# 3level_2NX_interleaved_boost_converter.net
KiCad netlist of a schematic drawn in EAGLE
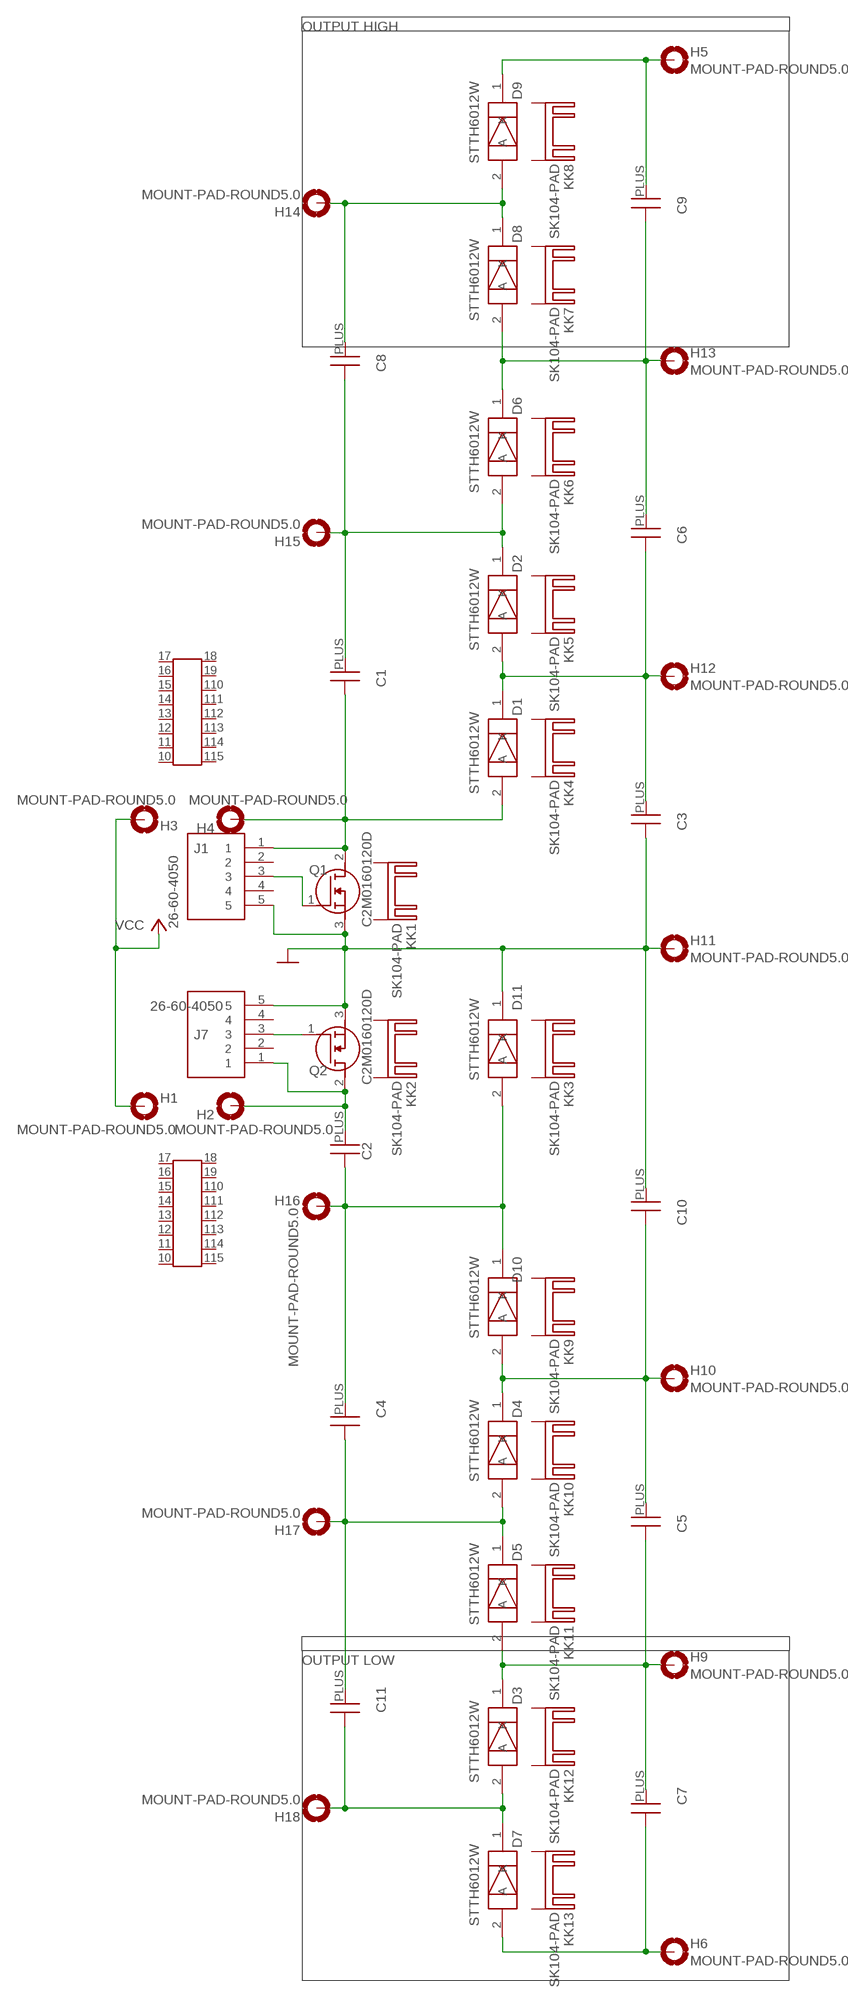
[diagram p0: schematic, sheet 1]
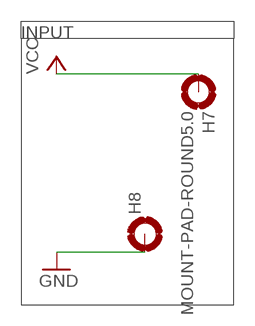
[diagram p1: schematic, sheet 2]

(export (version "E")
  (design (tool "Eeschema 10.0.6"))
  (components
    (comp (ref "H7")
      (value "MOUNT-PAD-ROUND5.0")
      (footprint "eagle-import:5,0-PAD")
      (libsource (lib "eagle-import") (part "MOUNT-PAD-ROUND5.0"))
    )
    (comp (ref "H8")
      (value "MOUNT-PAD-ROUND5.0")
      (footprint "eagle-import:5,0-PAD")
      (libsource (lib "eagle-import") (part "MOUNT-PAD-ROUND5.0"))
    )
    (comp (ref "C1")
      (value "SANJEECAP")
      (footprint "eagle-import:ECA2WHG2R2")
      (libsource (lib "eagle-import") (part "SANJEECAP"))
    )
    (comp (ref "C2")
      (value "SANJEECAP")
      (footprint "eagle-import:ECA2WHG2R2")
      (libsource (lib "eagle-import") (part "SANJEECAP"))
    )
    (comp (ref "C3")
      (value "SANJEECAP")
      (footprint "eagle-import:ECA2WHG2R2")
      (libsource (lib "eagle-import") (part "SANJEECAP"))
    )
    (comp (ref "C4")
      (value "SANJEECAP")
      (footprint "eagle-import:ECA2WHG2R2")
      (libsource (lib "eagle-import") (part "SANJEECAP"))
    )
    (comp (ref "C5")
      (value "SANJEECAP")
      (footprint "eagle-import:ECA2WHG2R2")
      (libsource (lib "eagle-import") (part "SANJEECAP"))
    )
    (comp (ref "C6")
      (value "SANJEECAP")
      (footprint "eagle-import:ECA2WHG2R2")
      (libsource (lib "eagle-import") (part "SANJEECAP"))
    )
    (comp (ref "C7")
      (value "SANJEECAP")
      (footprint "eagle-import:ECA2WHG2R2")
      (libsource (lib "eagle-import") (part "SANJEECAP"))
    )
    (comp (ref "C8")
      (value "SANJEECAP")
      (footprint "eagle-import:ECA2WHG2R2")
      (libsource (lib "eagle-import") (part "SANJEECAP"))
    )
    (comp (ref "C9")
      (value "SANJEECAP")
      (footprint "eagle-import:ECA2WHG2R2")
      (libsource (lib "eagle-import") (part "SANJEECAP"))
    )
    (comp (ref "C10")
      (value "SANJEECAP")
      (footprint "eagle-import:ECA2WHG2R2")
      (libsource (lib "eagle-import") (part "SANJEECAP"))
    )
    (comp (ref "C11")
      (value "SANJEECAP")
      (footprint "eagle-import:ECA2WHG2R2")
      (libsource (lib "eagle-import") (part "SANJEECAP"))
    )
    (comp (ref "D1")
      (value "STTH6012W")
      (footprint "eagle-import:TO1090P515X1560X2445-2P")
      (fields (field (name "RS_PART_NUMBER") "6870818"))
      (libsource (lib "eagle-import") (part "STTH6012W"))
    )
    (comp (ref "D2")
      (value "STTH6012W")
      (footprint "eagle-import:TO1090P515X1560X2445-2P")
      (fields (field (name "RS_PART_NUMBER") "6870818"))
      (libsource (lib "eagle-import") (part "STTH6012W"))
    )
    (comp (ref "D3")
      (value "STTH6012W")
      (footprint "eagle-import:TO1090P515X1560X2445-2P")
      (fields (field (name "RS_PART_NUMBER") "6870818"))
      (libsource (lib "eagle-import") (part "STTH6012W"))
    )
    (comp (ref "D4")
      (value "STTH6012W")
      (footprint "eagle-import:TO1090P515X1560X2445-2P")
      (fields (field (name "RS_PART_NUMBER") "6870818"))
      (libsource (lib "eagle-import") (part "STTH6012W"))
    )
    (comp (ref "D5")
      (value "STTH6012W")
      (footprint "eagle-import:TO1090P515X1560X2445-2P")
      (fields (field (name "RS_PART_NUMBER") "6870818"))
      (libsource (lib "eagle-import") (part "STTH6012W"))
    )
    (comp (ref "D6")
      (value "STTH6012W")
      (footprint "eagle-import:TO1090P515X1560X2445-2P")
      (fields (field (name "RS_PART_NUMBER") "6870818"))
      (libsource (lib "eagle-import") (part "STTH6012W"))
    )
    (comp (ref "D7")
      (value "STTH6012W")
      (footprint "eagle-import:TO1090P515X1560X2445-2P")
      (fields (field (name "RS_PART_NUMBER") "6870818"))
      (libsource (lib "eagle-import") (part "STTH6012W"))
    )
    (comp (ref "D8")
      (value "STTH6012W")
      (footprint "eagle-import:TO1090P515X1560X2445-2P")
      (fields (field (name "RS_PART_NUMBER") "6870818"))
      (libsource (lib "eagle-import") (part "STTH6012W"))
    )
    (comp (ref "D9")
      (value "STTH6012W")
      (footprint "eagle-import:TO1090P515X1560X2445-2P")
      (fields (field (name "RS_PART_NUMBER") "6870818"))
      (libsource (lib "eagle-import") (part "STTH6012W"))
    )
    (comp (ref "D10")
      (value "STTH6012W")
      (footprint "eagle-import:TO1090P515X1560X2445-2P")
      (fields (field (name "RS_PART_NUMBER") "6870818"))
      (libsource (lib "eagle-import") (part "STTH6012W"))
    )
    (comp (ref "D11")
      (value "STTH6012W")
      (footprint "eagle-import:TO1090P515X1560X2445-2P")
      (fields (field (name "RS_PART_NUMBER") "6870818"))
      (libsource (lib "eagle-import") (part "STTH6012W"))
    )
    (comp (ref "H1")
      (value "MOUNT-PAD-ROUND5.0")
      (footprint "eagle-import:5,0-PAD")
      (libsource (lib "eagle-import") (part "MOUNT-PAD-ROUND5.0"))
    )
    (comp (ref "H2")
      (value "MOUNT-PAD-ROUND5.0")
      (footprint "eagle-import:5,0-PAD")
      (libsource (lib "eagle-import") (part "MOUNT-PAD-ROUND5.0"))
    )
    (comp (ref "H3")
      (value "MOUNT-PAD-ROUND5.0")
      (footprint "eagle-import:5,0-PAD")
      (libsource (lib "eagle-import") (part "MOUNT-PAD-ROUND5.0"))
    )
    (comp (ref "H4")
      (value "MOUNT-PAD-ROUND5.0")
      (footprint "eagle-import:5,0-PAD")
      (libsource (lib "eagle-import") (part "MOUNT-PAD-ROUND5.0"))
    )
    (comp (ref "H5")
      (value "MOUNT-PAD-ROUND5.0")
      (footprint "eagle-import:5,0-PAD")
      (libsource (lib "eagle-import") (part "MOUNT-PAD-ROUND5.0"))
    )
    (comp (ref "H6")
      (value "MOUNT-PAD-ROUND5.0")
      (footprint "eagle-import:5,0-PAD")
      (libsource (lib "eagle-import") (part "MOUNT-PAD-ROUND5.0"))
    )
    (comp (ref "H9")
      (value "MOUNT-PAD-ROUND5.0")
      (footprint "eagle-import:5,0-PAD")
      (libsource (lib "eagle-import") (part "MOUNT-PAD-ROUND5.0"))
    )
    (comp (ref "H10")
      (value "MOUNT-PAD-ROUND5.0")
      (footprint "eagle-import:5,0-PAD")
      (libsource (lib "eagle-import") (part "MOUNT-PAD-ROUND5.0"))
    )
    (comp (ref "H11")
      (value "MOUNT-PAD-ROUND5.0")
      (footprint "eagle-import:5,0-PAD")
      (libsource (lib "eagle-import") (part "MOUNT-PAD-ROUND5.0"))
    )
    (comp (ref "H12")
      (value "MOUNT-PAD-ROUND5.0")
      (footprint "eagle-import:5,0-PAD")
      (libsource (lib "eagle-import") (part "MOUNT-PAD-ROUND5.0"))
    )
    (comp (ref "H13")
      (value "MOUNT-PAD-ROUND5.0")
      (footprint "eagle-import:5,0-PAD")
      (libsource (lib "eagle-import") (part "MOUNT-PAD-ROUND5.0"))
    )
    (comp (ref "H14")
      (value "MOUNT-PAD-ROUND5.0")
      (footprint "eagle-import:5,0-PAD")
      (libsource (lib "eagle-import") (part "MOUNT-PAD-ROUND5.0"))
    )
    (comp (ref "H15")
      (value "MOUNT-PAD-ROUND5.0")
      (footprint "eagle-import:5,0-PAD")
      (libsource (lib "eagle-import") (part "MOUNT-PAD-ROUND5.0"))
    )
    (comp (ref "H16")
      (value "MOUNT-PAD-ROUND5.0")
      (footprint "eagle-import:5,0-PAD")
      (libsource (lib "eagle-import") (part "MOUNT-PAD-ROUND5.0"))
    )
    (comp (ref "H17")
      (value "MOUNT-PAD-ROUND5.0")
      (footprint "eagle-import:5,0-PAD")
      (libsource (lib "eagle-import") (part "MOUNT-PAD-ROUND5.0"))
    )
    (comp (ref "H18")
      (value "MOUNT-PAD-ROUND5.0")
      (footprint "eagle-import:5,0-PAD")
      (libsource (lib "eagle-import") (part "MOUNT-PAD-ROUND5.0"))
    )
    (comp (ref "J1")
      (value "26-60-4050")
      (footprint "eagle-import:SHDR5W155P0X396_1X5_1966X1001X")
      (fields (field (name "MOUSER_PART_NUMBER") "538-26-60-4050"))
      (libsource (lib "eagle-import") (part "26-60-4050"))
    )
    (comp (ref "J7")
      (value "26-60-4050")
      (footprint "eagle-import:SHDR5W155P0X396_1X5_1966X1001X")
      (fields (field (name "MOUSER_PART_NUMBER") "538-26-60-4050"))
      (libsource (lib "eagle-import") (part "26-60-4050"))
    )
    (comp (ref "KK1")
      (value "SK104-PAD")
      (footprint "eagle-import:SK104-PAD")
      (libsource (lib "eagle-import") (part "SK104-PAD"))
    )
    (comp (ref "KK2")
      (value "SK104-PAD")
      (footprint "eagle-import:SK104-PAD")
      (libsource (lib "eagle-import") (part "SK104-PAD"))
    )
    (comp (ref "KK3")
      (value "SK104-PAD")
      (footprint "eagle-import:SK104-PAD")
      (libsource (lib "eagle-import") (part "SK104-PAD"))
    )
    (comp (ref "KK4")
      (value "SK104-PAD")
      (footprint "eagle-import:SK104-PAD")
      (libsource (lib "eagle-import") (part "SK104-PAD"))
    )
    (comp (ref "KK5")
      (value "SK104-PAD")
      (footprint "eagle-import:SK104-PAD")
      (libsource (lib "eagle-import") (part "SK104-PAD"))
    )
    (comp (ref "KK6")
      (value "SK104-PAD")
      (footprint "eagle-import:SK104-PAD")
      (libsource (lib "eagle-import") (part "SK104-PAD"))
    )
    (comp (ref "KK7")
      (value "SK104-PAD")
      (footprint "eagle-import:SK104-PAD")
      (libsource (lib "eagle-import") (part "SK104-PAD"))
    )
    (comp (ref "KK8")
      (value "SK104-PAD")
      (footprint "eagle-import:SK104-PAD")
      (libsource (lib "eagle-import") (part "SK104-PAD"))
    )
    (comp (ref "KK9")
      (value "SK104-PAD")
      (footprint "eagle-import:SK104-PAD")
      (libsource (lib "eagle-import") (part "SK104-PAD"))
    )
    (comp (ref "KK10")
      (value "SK104-PAD")
      (footprint "eagle-import:SK104-PAD")
      (libsource (lib "eagle-import") (part "SK104-PAD"))
    )
    (comp (ref "KK11")
      (value "SK104-PAD")
      (footprint "eagle-import:SK104-PAD")
      (libsource (lib "eagle-import") (part "SK104-PAD"))
    )
    (comp (ref "KK12")
      (value "SK104-PAD")
      (footprint "eagle-import:SK104-PAD")
      (libsource (lib "eagle-import") (part "SK104-PAD"))
    )
    (comp (ref "KK13")
      (value "SK104-PAD")
      (footprint "eagle-import:SK104-PAD")
      (libsource (lib "eagle-import") (part "SK104-PAD"))
    )
    (comp (ref "Q1")
      (value "C2M0160120D")
      (footprint "eagle-import:TO544P521X1594X2550-3P")
      (fields (field (name "RS_PART_NUMBER") "1629709"))
      (libsource (lib "eagle-import") (part "C2M0160120D"))
    )
    (comp (ref "Q2")
      (value "C2M0160120D")
      (footprint "eagle-import:TO544P521X1594X2550-3P")
      (fields (field (name "RS_PART_NUMBER") "1629709") (field (name "SPICEPREFIX") "Q"))
      (libsource (lib "eagle-import") (part "C2M0160120D"))
    )
    (comp (ref "U$1")
      (value "JELL")
      (footprint "eagle-import:BOBBIN")
      (libsource (lib "eagle-import") (part "JELL"))
    )
    (comp (ref "U$2")
      (value "JELL")
      (footprint "eagle-import:BOBBIN")
      (libsource (lib "eagle-import") (part "JELL"))
    )
  )
  (nets
    (net (code "1") (name "GND") (class "Default")
      (node (ref "C10") (pin "PLUS") (pinfunction "2_PLUS") (pintype "bidirectional"))
      (node (ref "C3") (pin "MINUS") (pinfunction "1_MINUS") (pintype "bidirectional"))
      (node (ref "D11") (pin "1") (pinfunction "K_1") (pintype "bidirectional"))
      (node (ref "H11") (pin "B5") (pinfunction "MOUNT_B5") (pintype "passive"))
      (node (ref "H8") (pin "B5") (pinfunction "MOUNT_B5") (pintype "passive"))
      (node (ref "J1") (pin "5") (pinfunction "5_5") (pintype "bidirectional"))
      (node (ref "J7") (pin "5") (pinfunction "5_5") (pintype "bidirectional"))
      (node (ref "Q1") (pin "3") (pinfunction "S_3") (pintype "bidirectional"))
      (node (ref "Q2") (pin "3") (pinfunction "S_3") (pintype "bidirectional"))
    )
    (net (code "2") (name "Net-(C1-1)") (class "Default")
      (node (ref "C1") (pin "MINUS") (pinfunction "1_MINUS") (pintype "bidirectional"))
      (node (ref "D1") (pin "2") (pinfunction "A_2") (pintype "bidirectional"))
      (node (ref "H4") (pin "B5") (pinfunction "MOUNT_B5") (pintype "passive"))
      (node (ref "J1") (pin "1") (pinfunction "1_1") (pintype "bidirectional"))
      (node (ref "Q1") (pin "2") (pinfunction "D_2") (pintype "bidirectional"))
    )
    (net (code "3") (name "Net-(C1-2)") (class "Default")
      (node (ref "C1") (pin "PLUS") (pinfunction "2_PLUS") (pintype "bidirectional"))
      (node (ref "C8") (pin "MINUS") (pinfunction "1_MINUS") (pintype "bidirectional"))
      (node (ref "D2") (pin "1") (pinfunction "K_1") (pintype "bidirectional"))
      (node (ref "D6") (pin "2") (pinfunction "A_2") (pintype "bidirectional"))
      (node (ref "H15") (pin "B5") (pinfunction "MOUNT_B5") (pintype "passive"))
    )
    (net (code "4") (name "Net-(C2-1)") (class "Default")
      (node (ref "C2") (pin "MINUS") (pinfunction "1_MINUS") (pintype "bidirectional"))
      (node (ref "C4") (pin "PLUS") (pinfunction "2_PLUS") (pintype "bidirectional"))
      (node (ref "D10") (pin "1") (pinfunction "K_1") (pintype "bidirectional"))
      (node (ref "D11") (pin "2") (pinfunction "A_2") (pintype "bidirectional"))
      (node (ref "H16") (pin "B5") (pinfunction "MOUNT_B5") (pintype "passive"))
    )
    (net (code "5") (name "Net-(C2-2)") (class "Default")
      (node (ref "C2") (pin "PLUS") (pinfunction "2_PLUS") (pintype "bidirectional"))
      (node (ref "H2") (pin "B5") (pinfunction "MOUNT_B5") (pintype "passive"))
      (node (ref "J7") (pin "1") (pinfunction "1_1") (pintype "bidirectional"))
      (node (ref "Q2") (pin "2") (pinfunction "D_2") (pintype "bidirectional"))
    )
    (net (code "6") (name "Net-(C3-2)") (class "Default")
      (node (ref "C3") (pin "PLUS") (pinfunction "2_PLUS") (pintype "bidirectional"))
      (node (ref "C6") (pin "MINUS") (pinfunction "1_MINUS") (pintype "bidirectional"))
      (node (ref "D1") (pin "1") (pinfunction "K_1") (pintype "bidirectional"))
      (node (ref "D2") (pin "2") (pinfunction "A_2") (pintype "bidirectional"))
      (node (ref "H12") (pin "B5") (pinfunction "MOUNT_B5") (pintype "passive"))
    )
    (net (code "7") (name "Net-(C5-1)") (class "Default")
      (node (ref "C5") (pin "MINUS") (pinfunction "1_MINUS") (pintype "bidirectional"))
      (node (ref "C7") (pin "PLUS") (pinfunction "2_PLUS") (pintype "bidirectional"))
      (node (ref "D3") (pin "1") (pinfunction "K_1") (pintype "bidirectional"))
      (node (ref "D5") (pin "2") (pinfunction "A_2") (pintype "bidirectional"))
      (node (ref "H9") (pin "B5") (pinfunction "MOUNT_B5") (pintype "passive"))
    )
    (net (code "8") (name "Net-(C6-2)") (class "Default")
      (node (ref "C6") (pin "PLUS") (pinfunction "2_PLUS") (pintype "bidirectional"))
      (node (ref "C9") (pin "MINUS") (pinfunction "1_MINUS") (pintype "bidirectional"))
      (node (ref "D6") (pin "1") (pinfunction "K_1") (pintype "bidirectional"))
      (node (ref "D8") (pin "2") (pinfunction "A_2") (pintype "bidirectional"))
      (node (ref "H13") (pin "B5") (pinfunction "MOUNT_B5") (pintype "passive"))
    )
    (net (code "9") (name "Net-(C7-1)") (class "Default")
      (node (ref "C7") (pin "MINUS") (pinfunction "1_MINUS") (pintype "bidirectional"))
      (node (ref "D7") (pin "2") (pinfunction "A_2") (pintype "bidirectional"))
      (node (ref "H6") (pin "B5") (pinfunction "MOUNT_B5") (pintype "passive"))
    )
    (net (code "10") (name "Net-(C8-2)") (class "Default")
      (node (ref "C8") (pin "PLUS") (pinfunction "2_PLUS") (pintype "bidirectional"))
      (node (ref "D8") (pin "1") (pinfunction "K_1") (pintype "bidirectional"))
      (node (ref "D9") (pin "2") (pinfunction "A_2") (pintype "bidirectional"))
      (node (ref "H14") (pin "B5") (pinfunction "MOUNT_B5") (pintype "passive"))
    )
    (net (code "11") (name "Net-(C9-2)") (class "Default")
      (node (ref "C9") (pin "PLUS") (pinfunction "2_PLUS") (pintype "bidirectional"))
      (node (ref "D9") (pin "1") (pinfunction "K_1") (pintype "bidirectional"))
      (node (ref "H5") (pin "B5") (pinfunction "MOUNT_B5") (pintype "passive"))
    )
    (net (code "12") (name "Net-(C10-1)") (class "Default")
      (node (ref "C10") (pin "MINUS") (pinfunction "1_MINUS") (pintype "bidirectional"))
      (node (ref "C5") (pin "PLUS") (pinfunction "2_PLUS") (pintype "bidirectional"))
      (node (ref "D10") (pin "2") (pinfunction "A_2") (pintype "bidirectional"))
      (node (ref "D4") (pin "1") (pinfunction "K_1") (pintype "bidirectional"))
      (node (ref "H10") (pin "B5") (pinfunction "MOUNT_B5") (pintype "passive"))
    )
    (net (code "13") (name "Net-(C11-1)") (class "Default")
      (node (ref "C11") (pin "MINUS") (pinfunction "1_MINUS") (pintype "bidirectional"))
      (node (ref "D3") (pin "2") (pinfunction "A_2") (pintype "bidirectional"))
      (node (ref "D7") (pin "1") (pinfunction "K_1") (pintype "bidirectional"))
      (node (ref "H18") (pin "B5") (pinfunction "MOUNT_B5") (pintype "passive"))
    )
    (net (code "14") (name "Net-(C11-2)") (class "Default")
      (node (ref "C11") (pin "PLUS") (pinfunction "2_PLUS") (pintype "bidirectional"))
      (node (ref "C4") (pin "MINUS") (pinfunction "1_MINUS") (pintype "bidirectional"))
      (node (ref "D4") (pin "2") (pinfunction "A_2") (pintype "bidirectional"))
      (node (ref "D5") (pin "1") (pinfunction "K_1") (pintype "bidirectional"))
      (node (ref "H17") (pin "B5") (pinfunction "MOUNT_B5") (pintype "passive"))
    )
    (net (code "15") (name "Net-(Q1-G)") (class "Default")
      (node (ref "J1") (pin "3") (pinfunction "3_3") (pintype "bidirectional"))
      (node (ref "Q1") (pin "1") (pinfunction "G_1") (pintype "bidirectional"))
    )
    (net (code "16") (name "Net-(Q2-G)") (class "Default")
      (node (ref "J7") (pin "3") (pinfunction "3_3") (pintype "bidirectional"))
      (node (ref "Q2") (pin "1") (pinfunction "G_1") (pintype "bidirectional"))
    )
    (net (code "17") (name "VCC") (class "Default")
      (node (ref "H1") (pin "B5") (pinfunction "MOUNT_B5") (pintype "passive"))
      (node (ref "H3") (pin "B5") (pinfunction "MOUNT_B5") (pintype "passive"))
      (node (ref "H7") (pin "B5") (pinfunction "MOUNT_B5") (pintype "passive"))
    )
    (net (code "18") (name "unconnected-(J1-Pad2)") (class "Default")
      (node (ref "J1") (pin "2") (pinfunction "2_2") (pintype "bidirectional"))
    )
    (net (code "19") (name "unconnected-(J1-Pad4)") (class "Default")
      (node (ref "J1") (pin "4") (pinfunction "4_4") (pintype "bidirectional"))
    )
    (net (code "20") (name "unconnected-(J7-Pad2)") (class "Default")
      (node (ref "J7") (pin "2") (pinfunction "2_2") (pintype "bidirectional"))
    )
    (net (code "21") (name "unconnected-(J7-Pad4)") (class "Default")
      (node (ref "J7") (pin "4") (pinfunction "4_4") (pintype "bidirectional"))
    )
    (net (code "22") (name "unconnected-(KK1-K-PadK1)") (class "Default")
      (node (ref "KK1") (pin "K1") (pinfunction "K_K1") (pintype "passive"))
    )
    (net (code "23") (name "unconnected-(KK1-K-PadK2)") (class "Default")
      (node (ref "KK1") (pin "K2") (pinfunction "K_K2") (pintype "passive"))
    )
    (net (code "24") (name "unconnected-(KK2-K-PadK1)") (class "Default")
      (node (ref "KK2") (pin "K1") (pinfunction "K_K1") (pintype "passive"))
    )
    (net (code "25") (name "unconnected-(KK2-K-PadK2)") (class "Default")
      (node (ref "KK2") (pin "K2") (pinfunction "K_K2") (pintype "passive"))
    )
    (net (code "26") (name "unconnected-(KK3-K-PadK1)") (class "Default")
      (node (ref "KK3") (pin "K1") (pinfunction "K_K1") (pintype "passive"))
    )
    (net (code "27") (name "unconnected-(KK3-K-PadK2)") (class "Default")
      (node (ref "KK3") (pin "K2") (pinfunction "K_K2") (pintype "passive"))
    )
    (net (code "28") (name "unconnected-(KK4-K-PadK1)") (class "Default")
      (node (ref "KK4") (pin "K1") (pinfunction "K_K1") (pintype "passive"))
    )
    (net (code "29") (name "unconnected-(KK4-K-PadK2)") (class "Default")
      (node (ref "KK4") (pin "K2") (pinfunction "K_K2") (pintype "passive"))
    )
    (net (code "30") (name "unconnected-(KK5-K-PadK1)") (class "Default")
      (node (ref "KK5") (pin "K1") (pinfunction "K_K1") (pintype "passive"))
    )
    (net (code "31") (name "unconnected-(KK5-K-PadK2)") (class "Default")
      (node (ref "KK5") (pin "K2") (pinfunction "K_K2") (pintype "passive"))
    )
    (net (code "32") (name "unconnected-(KK6-K-PadK1)") (class "Default")
      (node (ref "KK6") (pin "K1") (pinfunction "K_K1") (pintype "passive"))
    )
    (net (code "33") (name "unconnected-(KK6-K-PadK2)") (class "Default")
      (node (ref "KK6") (pin "K2") (pinfunction "K_K2") (pintype "passive"))
    )
    (net (code "34") (name "unconnected-(KK7-K-PadK1)") (class "Default")
      (node (ref "KK7") (pin "K1") (pinfunction "K_K1") (pintype "passive"))
    )
    (net (code "35") (name "unconnected-(KK7-K-PadK2)") (class "Default")
      (node (ref "KK7") (pin "K2") (pinfunction "K_K2") (pintype "passive"))
    )
    (net (code "36") (name "unconnected-(KK8-K-PadK1)") (class "Default")
      (node (ref "KK8") (pin "K1") (pinfunction "K_K1") (pintype "passive"))
    )
    (net (code "37") (name "unconnected-(KK8-K-PadK2)") (class "Default")
      (node (ref "KK8") (pin "K2") (pinfunction "K_K2") (pintype "passive"))
    )
    (net (code "38") (name "unconnected-(KK9-K-PadK1)") (class "Default")
      (node (ref "KK9") (pin "K1") (pinfunction "K_K1") (pintype "passive"))
    )
    (net (code "39") (name "unconnected-(KK9-K-PadK2)") (class "Default")
      (node (ref "KK9") (pin "K2") (pinfunction "K_K2") (pintype "passive"))
    )
    (net (code "40") (name "unconnected-(KK10-K-PadK1)") (class "Default")
      (node (ref "KK10") (pin "K1") (pinfunction "K_K1") (pintype "passive"))
    )
    (net (code "41") (name "unconnected-(KK10-K-PadK2)") (class "Default")
      (node (ref "KK10") (pin "K2") (pinfunction "K_K2") (pintype "passive"))
    )
    (net (code "42") (name "unconnected-(KK11-K-PadK1)") (class "Default")
      (node (ref "KK11") (pin "K1") (pinfunction "K_K1") (pintype "passive"))
    )
    (net (code "43") (name "unconnected-(KK11-K-PadK2)") (class "Default")
      (node (ref "KK11") (pin "K2") (pinfunction "K_K2") (pintype "passive"))
    )
    (net (code "44") (name "unconnected-(KK12-K-PadK1)") (class "Default")
      (node (ref "KK12") (pin "K1") (pinfunction "K_K1") (pintype "passive"))
    )
    (net (code "45") (name "unconnected-(KK12-K-PadK2)") (class "Default")
      (node (ref "KK12") (pin "K2") (pinfunction "K_K2") (pintype "passive"))
    )
    (net (code "46") (name "unconnected-(KK13-K-PadK1)") (class "Default")
      (node (ref "KK13") (pin "K1") (pinfunction "K_K1") (pintype "passive"))
    )
    (net (code "47") (name "unconnected-(KK13-K-PadK2)") (class "Default")
      (node (ref "KK13") (pin "K2") (pinfunction "K_K2") (pintype "passive"))
    )
    (net (code "48") (name "unconnected-(U$1-P$1-Pad10)") (class "Default")
      (node (ref "U$1") (pin "10") (pinfunction "P$1_10") (pintype "bidirectional"))
    )
    (net (code "49") (name "unconnected-(U$1-P$2-Pad11)") (class "Default")
      (node (ref "U$1") (pin "11") (pinfunction "P$2_11") (pintype "bidirectional"))
    )
    (net (code "50") (name "unconnected-(U$1-P$3-Pad12)") (class "Default")
      (node (ref "U$1") (pin "12") (pinfunction "P$3_12") (pintype "bidirectional"))
    )
    (net (code "51") (name "unconnected-(U$1-P$4-Pad13)") (class "Default")
      (node (ref "U$1") (pin "13") (pinfunction "P$4_13") (pintype "bidirectional"))
    )
    (net (code "52") (name "unconnected-(U$1-P$5-Pad14)") (class "Default")
      (node (ref "U$1") (pin "14") (pinfunction "P$5_14") (pintype "bidirectional"))
    )
    (net (code "53") (name "unconnected-(U$1-P$6-Pad15)") (class "Default")
      (node (ref "U$1") (pin "15") (pinfunction "P$6_15") (pintype "bidirectional"))
    )
    (net (code "54") (name "unconnected-(U$1-P$7-Pad16)") (class "Default")
      (node (ref "U$1") (pin "16") (pinfunction "P$7_16") (pintype "bidirectional"))
    )
    (net (code "55") (name "unconnected-(U$1-P$8-Pad17)") (class "Default")
      (node (ref "U$1") (pin "17") (pinfunction "P$8_17") (pintype "bidirectional"))
    )
    (net (code "56") (name "unconnected-(U$1-P$9-Pad18)") (class "Default")
      (node (ref "U$1") (pin "18") (pinfunction "P$9_18") (pintype "bidirectional"))
    )
    (net (code "57") (name "unconnected-(U$1-P$10-Pad19)") (class "Default")
      (node (ref "U$1") (pin "19") (pinfunction "P$10_19") (pintype "bidirectional"))
    )
    (net (code "58") (name "unconnected-(U$1-P$11-Pad110)") (class "Default")
      (node (ref "U$1") (pin "110") (pinfunction "P$11_110") (pintype "bidirectional"))
    )
    (net (code "59") (name "unconnected-(U$1-P$12-Pad111)") (class "Default")
      (node (ref "U$1") (pin "111") (pinfunction "P$12_111") (pintype "bidirectional"))
    )
    (net (code "60") (name "unconnected-(U$1-P$13-Pad112)") (class "Default")
      (node (ref "U$1") (pin "112") (pinfunction "P$13_112") (pintype "bidirectional"))
    )
    (net (code "61") (name "unconnected-(U$1-P$14-Pad113)") (class "Default")
      (node (ref "U$1") (pin "113") (pinfunction "P$14_113") (pintype "bidirectional"))
    )
    (net (code "62") (name "unconnected-(U$1-P$15-Pad114)") (class "Default")
      (node (ref "U$1") (pin "114") (pinfunction "P$15_114") (pintype "bidirectional"))
    )
    (net (code "63") (name "unconnected-(U$1-P$16-Pad115)") (class "Default")
      (node (ref "U$1") (pin "115") (pinfunction "P$16_115") (pintype "bidirectional"))
    )
    (net (code "64") (name "unconnected-(U$2-P$1-Pad10)") (class "Default")
      (node (ref "U$2") (pin "10") (pinfunction "P$1_10") (pintype "bidirectional"))
    )
    (net (code "65") (name "unconnected-(U$2-P$2-Pad11)") (class "Default")
      (node (ref "U$2") (pin "11") (pinfunction "P$2_11") (pintype "bidirectional"))
    )
    (net (code "66") (name "unconnected-(U$2-P$3-Pad12)") (class "Default")
      (node (ref "U$2") (pin "12") (pinfunction "P$3_12") (pintype "bidirectional"))
    )
    (net (code "67") (name "unconnected-(U$2-P$4-Pad13)") (class "Default")
      (node (ref "U$2") (pin "13") (pinfunction "P$4_13") (pintype "bidirectional"))
    )
    (net (code "68") (name "unconnected-(U$2-P$5-Pad14)") (class "Default")
      (node (ref "U$2") (pin "14") (pinfunction "P$5_14") (pintype "bidirectional"))
    )
    (net (code "69") (name "unconnected-(U$2-P$6-Pad15)") (class "Default")
      (node (ref "U$2") (pin "15") (pinfunction "P$6_15") (pintype "bidirectional"))
    )
    (net (code "70") (name "unconnected-(U$2-P$7-Pad16)") (class "Default")
      (node (ref "U$2") (pin "16") (pinfunction "P$7_16") (pintype "bidirectional"))
    )
    (net (code "71") (name "unconnected-(U$2-P$8-Pad17)") (class "Default")
      (node (ref "U$2") (pin "17") (pinfunction "P$8_17") (pintype "bidirectional"))
    )
    (net (code "72") (name "unconnected-(U$2-P$9-Pad18)") (class "Default")
      (node (ref "U$2") (pin "18") (pinfunction "P$9_18") (pintype "bidirectional"))
    )
    (net (code "73") (name "unconnected-(U$2-P$10-Pad19)") (class "Default")
      (node (ref "U$2") (pin "19") (pinfunction "P$10_19") (pintype "bidirectional"))
    )
    (net (code "74") (name "unconnected-(U$2-P$11-Pad110)") (class "Default")
      (node (ref "U$2") (pin "110") (pinfunction "P$11_110") (pintype "bidirectional"))
    )
    (net (code "75") (name "unconnected-(U$2-P$12-Pad111)") (class "Default")
      (node (ref "U$2") (pin "111") (pinfunction "P$12_111") (pintype "bidirectional"))
    )
    (net (code "76") (name "unconnected-(U$2-P$13-Pad112)") (class "Default")
      (node (ref "U$2") (pin "112") (pinfunction "P$13_112") (pintype "bidirectional"))
    )
    (net (code "77") (name "unconnected-(U$2-P$14-Pad113)") (class "Default")
      (node (ref "U$2") (pin "113") (pinfunction "P$14_113") (pintype "bidirectional"))
    )
    (net (code "78") (name "unconnected-(U$2-P$15-Pad114)") (class "Default")
      (node (ref "U$2") (pin "114") (pinfunction "P$15_114") (pintype "bidirectional"))
    )
    (net (code "79") (name "unconnected-(U$2-P$16-Pad115)") (class "Default")
      (node (ref "U$2") (pin "115") (pinfunction "P$16_115") (pintype "bidirectional"))
    )
  )
)
